# ProPrj_LowFreqInverter_2025-11-08.net
KiCad netlist of a schematic drawn in EasyEDA Pro
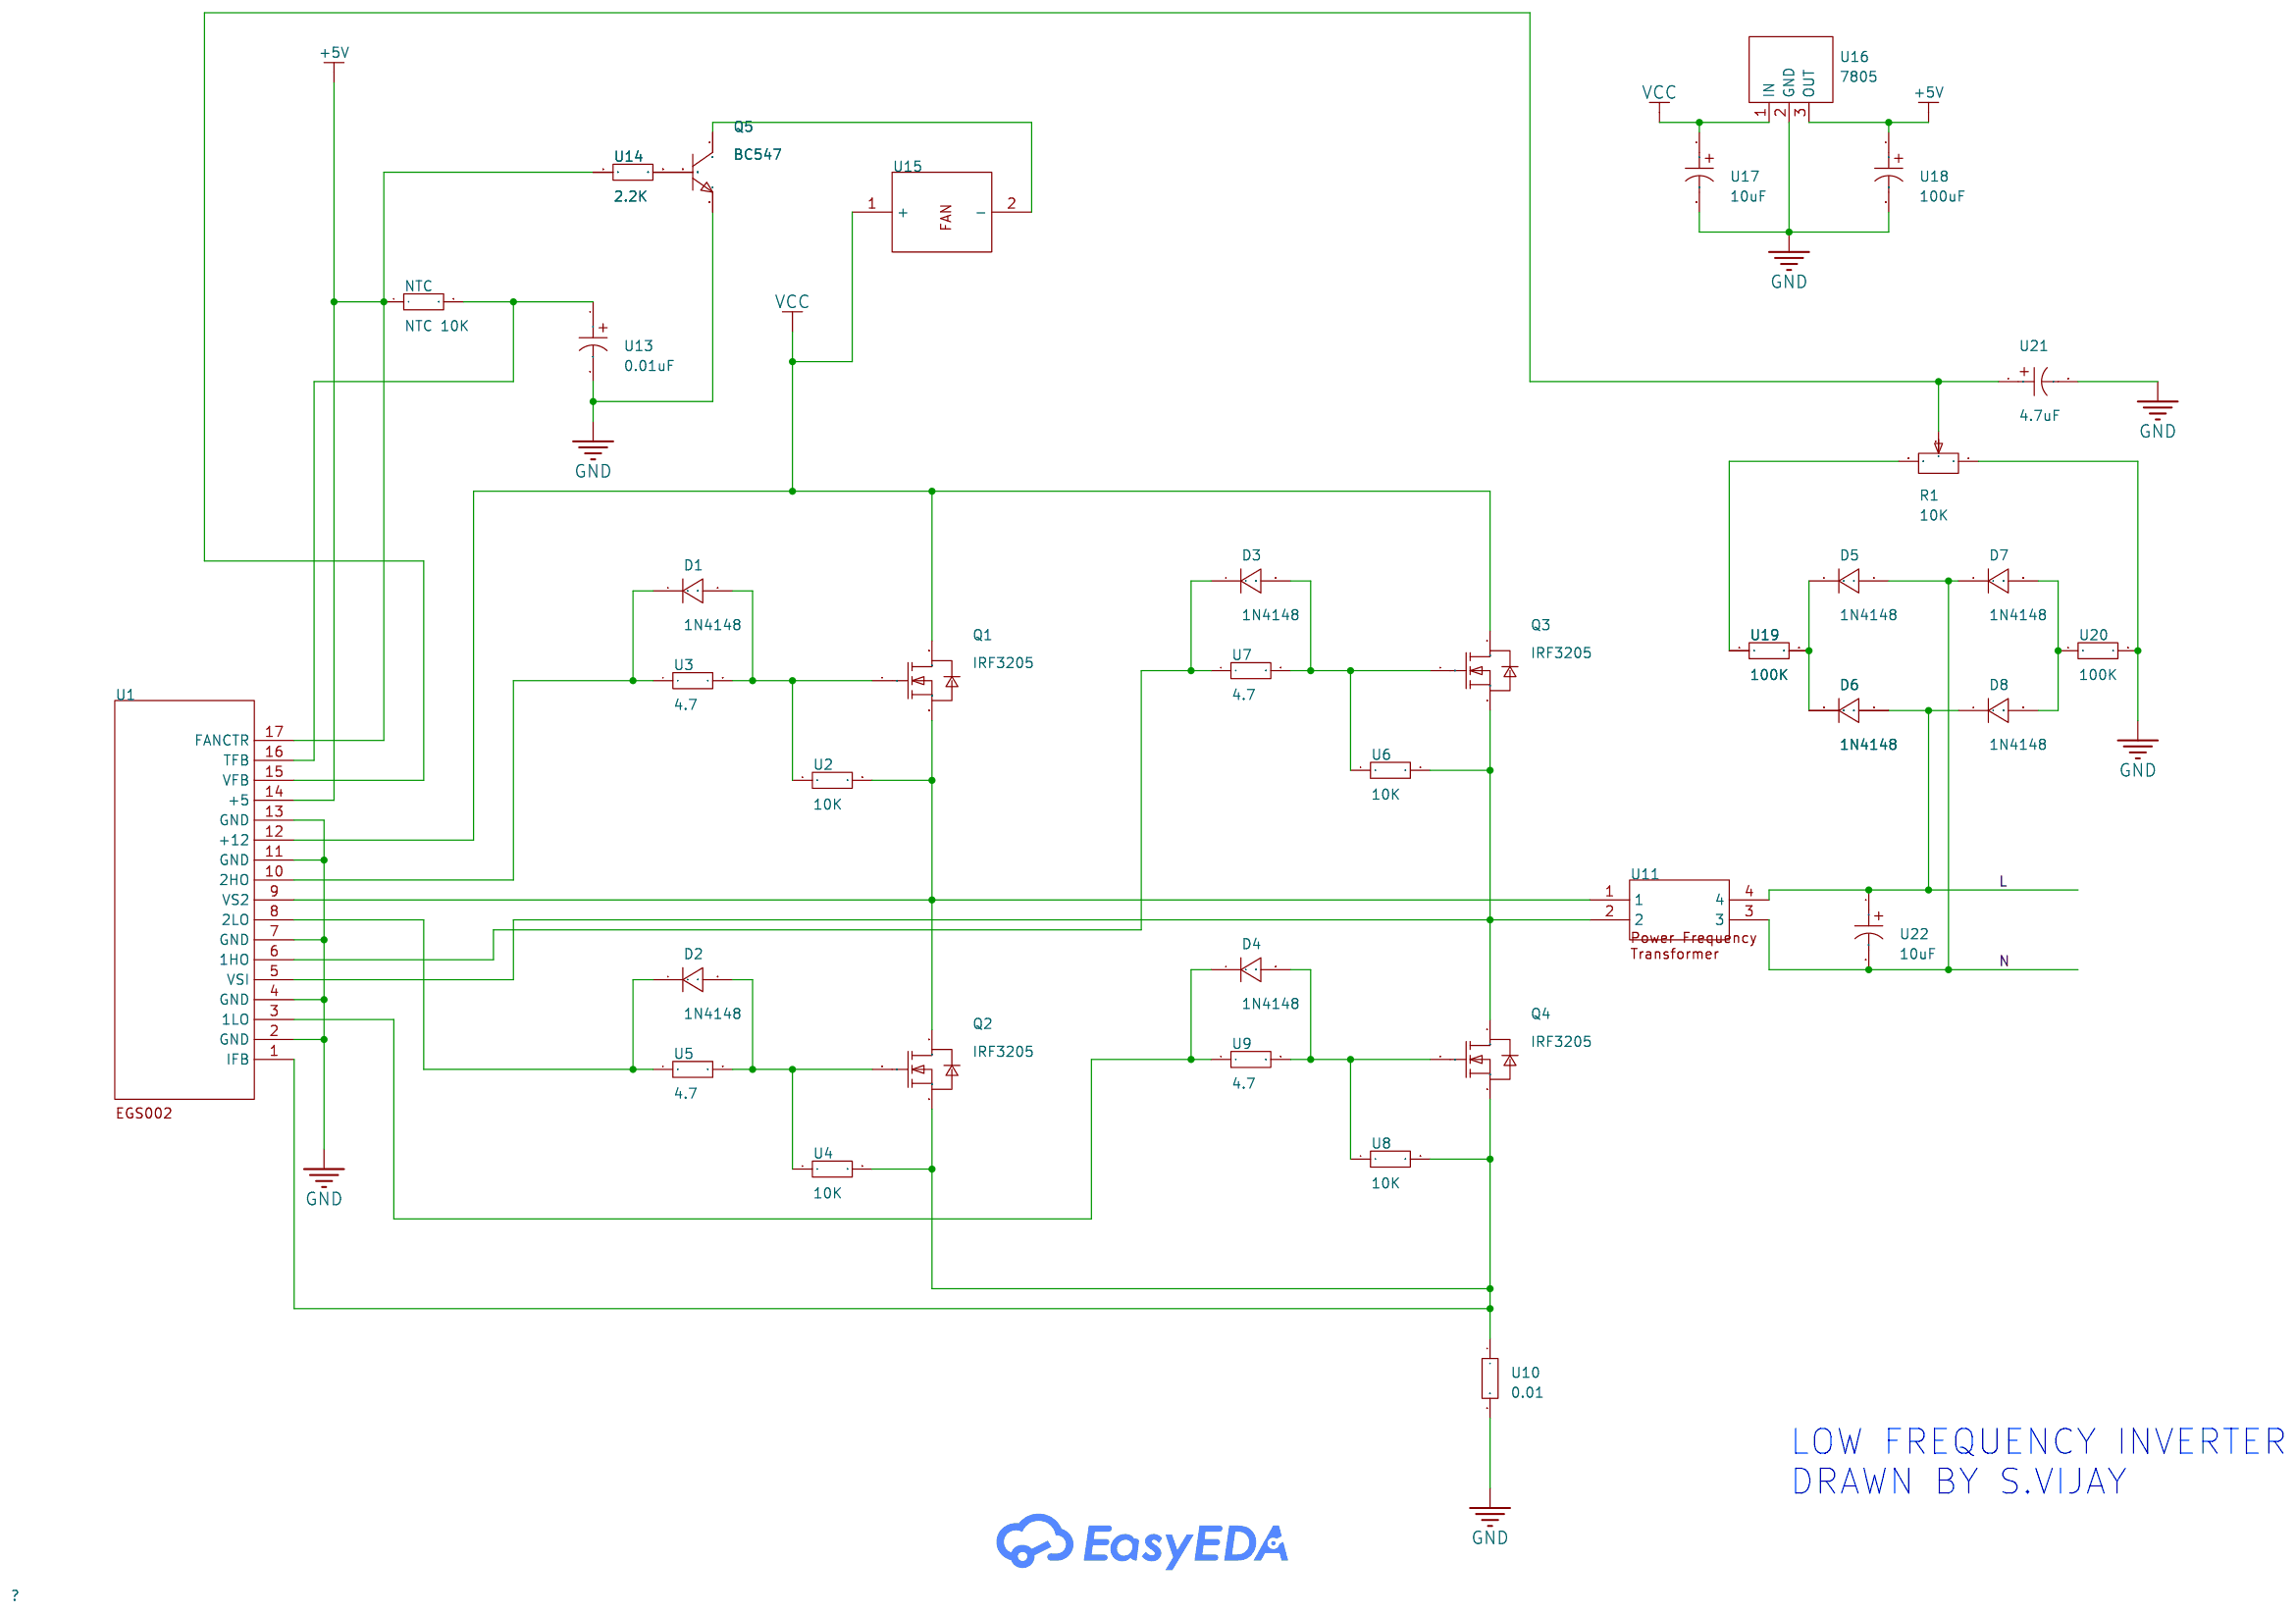
[diagram p0: schematic sheet]

(export (version "E")
  (design (tool "Eeschema 10.0.6"))
  (components
    (comp (ref "D1")
      (value "1N4148")
      (footprint "easyedapro:DO-35_BD2.0-L4.0-P8.0-D0.5-RD")
      (libsource (lib "easyedapro") (part "1N4148_C13769"))
    )
    (comp (ref "D2")
      (value "1N4148")
      (footprint "easyedapro:DO-35_BD2.0-L4.0-P8.0-D0.5-RD")
      (libsource (lib "easyedapro") (part "1N4148_C13769"))
    )
    (comp (ref "D3")
      (value "1N4148")
      (footprint "easyedapro:DO-35_BD2.0-L4.0-P8.0-D0.5-RD")
      (libsource (lib "easyedapro") (part "1N4148_C13769"))
    )
    (comp (ref "D4")
      (value "1N4148")
      (footprint "easyedapro:DO-35_BD2.0-L4.0-P8.0-D0.5-RD")
      (libsource (lib "easyedapro") (part "1N4148_C13769"))
    )
    (comp (ref "D5")
      (value "1N4148")
      (footprint "easyedapro:DO-35_BD2.0-L4.0-P8.0-D0.5-RD")
      (libsource (lib "easyedapro") (part "1N4148_C13769"))
    )
    (comp (ref "D6")
      (value "1N4148")
      (footprint "easyedapro:DO-35_BD2.0-L4.0-P8.0-D0.5-RD")
      (libsource (lib "easyedapro") (part "1N4148_C13769"))
    )
    (comp (ref "D7")
      (value "1N4148")
      (footprint "easyedapro:DO-35_BD2.0-L4.0-P8.0-D0.5-RD")
      (libsource (lib "easyedapro") (part "1N4148_C13769"))
    )
    (comp (ref "D8")
      (value "1N4148")
      (footprint "easyedapro:DO-35_BD2.0-L4.0-P8.0-D0.5-RD")
      (libsource (lib "easyedapro") (part "1N4148_C13769"))
    )
    (comp (ref "NTC")
      (value "NTC 10K")
      (footprint "easyedapro:RES-TH_BD2.3-L6.5-P10.50-D0.5")
      (fields (field (name "Manufacturer Part") "RES1/4W47K"))
      (libsource (lib "easyedapro") (part "RES1/4W47K"))
    )
    (comp (ref "Q1")
      (value "IRF3205")
      (footprint "easyedapro:TO-220-3_L10.0-W4.6-P2.54-L")
      (fields (field (name "Manufacturer") "minos(迈诺斯)"))
      (libsource (lib "easyedapro") (part "IRF3205"))
    )
    (comp (ref "Q2")
      (value "IRF3205")
      (footprint "easyedapro:TO-220-3_L10.0-W4.6-P2.54-L")
      (fields (field (name "Manufacturer") "minos(迈诺斯)"))
      (libsource (lib "easyedapro") (part "IRF3205"))
    )
    (comp (ref "Q3")
      (value "IRF3205")
      (footprint "easyedapro:TO-220-3_L10.0-W4.6-P2.54-L")
      (fields (field (name "Manufacturer") "minos(迈诺斯)"))
      (libsource (lib "easyedapro") (part "IRF3205"))
    )
    (comp (ref "Q4")
      (value "IRF3205")
      (footprint "easyedapro:TO-220-3_L10.0-W4.6-P2.54-L")
      (fields (field (name "Manufacturer") "minos(迈诺斯)"))
      (libsource (lib "easyedapro") (part "IRF3205"))
    )
    (comp (ref "Q5")
      (value "BC547")
      (footprint "easyedapro:TO-92-3_L4.9-W3.7-P1.27-L")
      (fields (field (name "Manufacturer") "CJ(江苏长电/长晶)"))
      (libsource (lib "easyedapro") (part "BC547_C47089404"))
    )
    (comp (ref "R1")
      (value "10K")
      (footprint "easyedapro:RES-ADJ-TH_3296W")
      (libsource (lib "easyedapro") (part "3296W-2K"))
    )
    (comp (ref "U1")
      (value "~")
      (footprint "easyedapro:EGS002")
      (libsource (lib "easyedapro") (part "EGS002"))
    )
    (comp (ref "U2")
      (value "10K")
      (footprint "easyedapro:RES-TH_BD2.3-L6.5-P10.50-D0.5")
      (fields (field (name "Manufacturer Part") "RES1/4W47K"))
      (libsource (lib "easyedapro") (part "RES1/4W47K"))
    )
    (comp (ref "U3")
      (value "4.7")
      (footprint "easyedapro:RES-TH_BD2.3-L6.5-P10.50-D0.5")
      (libsource (lib "easyedapro") (part "RES1/4W47K"))
    )
    (comp (ref "U4")
      (value "10K")
      (footprint "easyedapro:RES-TH_BD2.3-L6.5-P10.50-D0.5")
      (fields (field (name "Manufacturer Part") "RES1/4W47K"))
      (libsource (lib "easyedapro") (part "RES1/4W47K"))
    )
    (comp (ref "U5")
      (value "4.7")
      (footprint "easyedapro:RES-TH_BD2.3-L6.5-P10.50-D0.5")
      (libsource (lib "easyedapro") (part "RES1/4W47K"))
    )
    (comp (ref "U6")
      (value "10K")
      (footprint "easyedapro:RES-TH_BD2.3-L6.5-P10.50-D0.5")
      (fields (field (name "Manufacturer Part") "RES1/4W47K"))
      (libsource (lib "easyedapro") (part "RES1/4W47K"))
    )
    (comp (ref "U7")
      (value "4.7")
      (footprint "easyedapro:RES-TH_BD2.3-L6.5-P10.50-D0.5")
      (libsource (lib "easyedapro") (part "RES1/4W47K"))
    )
    (comp (ref "U8")
      (value "10K")
      (footprint "easyedapro:RES-TH_BD2.3-L6.5-P10.50-D0.5")
      (fields (field (name "Manufacturer Part") "RES1/4W47K"))
      (libsource (lib "easyedapro") (part "RES1/4W47K"))
    )
    (comp (ref "U9")
      (value "4.7")
      (footprint "easyedapro:RES-TH_BD2.3-L6.5-P10.50-D0.5")
      (libsource (lib "easyedapro") (part "RES1/4W47K"))
    )
    (comp (ref "U10")
      (value "0.01")
      (footprint "easyedapro:RES-TH_BD2.3-L6.5-P10.50-D0.5")
      (libsource (lib "easyedapro") (part "RES1/4W47K"))
    )
    (comp (ref "U11")
      (value "~")
      (footprint "easyedapro:Power Frequency Transformer")
      (libsource (lib "easyedapro") (part "Power Frequency Transformer"))
    )
    (comp (ref "U13")
      (value "0.01uF")
      (footprint "easyedapro:CAP-TH_BD5.0-P2.00-D0.6-FD")
      (libsource (lib "easyedapro") (part "CE2.5MM-4.7UF 50V"))
    )
    (comp (ref "U14")
      (value "2.2K")
      (footprint "easyedapro:RES-TH_BD2.3-L6.5-P10.50-D0.5")
      (fields (field (name "Manufacturer Part") "RES1/4W47K"))
      (libsource (lib "easyedapro") (part "RES1/4W47K"))
    )
    (comp (ref "U15") (value "~") (footprint "easyedapro:FAN") (libsource (lib "easyedapro") (part "FAN")))
    (comp (ref "U16")
      (value "7805")
      (footprint "easyedapro:TO-220-3_L10.2-W4.5-P2.54-L")
      (libsource (lib "easyedapro") (part "7805_C2941265"))
    )
    (comp (ref "U17")
      (value "10uF")
      (footprint "easyedapro:CAP-TH_BD5.0-P2.00-D0.6-FD")
      (libsource (lib "easyedapro") (part "CE2.5MM-4.7UF 50V"))
    )
    (comp (ref "U18")
      (value "100uF")
      (footprint "easyedapro:CAP-TH_BD5.0-P2.00-D0.6-FD")
      (libsource (lib "easyedapro") (part "CE2.5MM-4.7UF 50V"))
    )
    (comp (ref "U19")
      (value "100K")
      (footprint "easyedapro:RES-TH_BD2.3-L6.5-P10.50-D0.5")
      (fields (field (name "Manufacturer Part") "RES1/4W47K"))
      (libsource (lib "easyedapro") (part "RES1/4W47K"))
    )
    (comp (ref "U20")
      (value "100K")
      (footprint "easyedapro:RES-TH_BD2.3-L6.5-P10.50-D0.5")
      (fields (field (name "Manufacturer Part") "RES1/4W47K"))
      (libsource (lib "easyedapro") (part "RES1/4W47K"))
    )
    (comp (ref "U21")
      (value "4.7uF")
      (footprint "easyedapro:CAP-TH_BD5.0-P2.00-D0.6-FD")
      (libsource (lib "easyedapro") (part "CE2.5MM-4.7UF 50V"))
    )
    (comp (ref "U22")
      (value "10uF")
      (footprint "easyedapro:CAP-TH_BD5.0-P2.00-D0.6-FD")
      (libsource (lib "easyedapro") (part "CE2.5MM-4.7UF 50V"))
    )
  )
  (nets
    (net (code "1") (name "+5V") (class "Default")
      (node (ref "NTC") (pin "1") (pinfunction "1_1") (pintype "input"))
      (node (ref "U1") (pin "14") (pinfunction "+5_14") (pintype "input"))
      (node (ref "U1") (pin "17") (pinfunction "FANCTR_17") (pintype "input"))
      (node (ref "U14") (pin "1") (pinfunction "1_1") (pintype "input"))
      (node (ref "U16") (pin "3") (pinfunction "OUT_3") (pintype "unspecified"))
      (node (ref "U18") (pin "1") (pinfunction "1_1") (pintype "input"))
    )
    (net (code "2") (name "/L") (class "Default")
      (node (ref "D6") (pin "2") (pinfunction "2_2") (pintype "unspecified"))
      (node (ref "D8") (pin "1") (pinfunction "1_1") (pintype "unspecified"))
      (node (ref "U11") (pin "4") (pinfunction "4_4") (pintype "input"))
      (node (ref "U22") (pin "1") (pinfunction "1_1") (pintype "input"))
    )
    (net (code "3") (name "/N") (class "Default")
      (node (ref "D5") (pin "2") (pinfunction "2_2") (pintype "unspecified"))
      (node (ref "D7") (pin "1") (pinfunction "1_1") (pintype "unspecified"))
      (node (ref "U11") (pin "3") (pinfunction "3_3") (pintype "input"))
      (node (ref "U22") (pin "2") (pinfunction "2_2") (pintype "input"))
    )
    (net (code "4") (name "GND") (class "Default")
      (node (ref "Q5") (pin "3") (pinfunction "E_3") (pintype "input"))
      (node (ref "R1") (pin "1") (pinfunction "1_1") (pintype "input"))
      (node (ref "U1") (pin "11") (pinfunction "GND_11") (pintype "input"))
      (node (ref "U1") (pin "13") (pinfunction "GND_13") (pintype "input"))
      (node (ref "U1") (pin "2") (pinfunction "GND_2") (pintype "input"))
      (node (ref "U1") (pin "4") (pinfunction "GND_4") (pintype "input"))
      (node (ref "U1") (pin "7") (pinfunction "GND_7") (pintype "input"))
      (node (ref "U10") (pin "2") (pinfunction "2_2") (pintype "input"))
      (node (ref "U13") (pin "2") (pinfunction "2_2") (pintype "input"))
      (node (ref "U16") (pin "2") (pinfunction "GND_2") (pintype "unspecified"))
      (node (ref "U17") (pin "2") (pinfunction "2_2") (pintype "input"))
      (node (ref "U18") (pin "2") (pinfunction "2_2") (pintype "input"))
      (node (ref "U20") (pin "2") (pinfunction "2_2") (pintype "input"))
      (node (ref "U21") (pin "2") (pinfunction "2_2") (pintype "input"))
    )
    (net (code "5") (name "Net-(D5-Pad1)") (class "Default")
      (node (ref "D5") (pin "1") (pinfunction "1_1") (pintype "unspecified"))
      (node (ref "D6") (pin "1") (pinfunction "1_1") (pintype "unspecified"))
      (node (ref "U19") (pin "2") (pinfunction "2_2") (pintype "input"))
    )
    (net (code "6") (name "Net-(D7-Pad2)") (class "Default")
      (node (ref "D7") (pin "2") (pinfunction "2_2") (pintype "unspecified"))
      (node (ref "D8") (pin "2") (pinfunction "2_2") (pintype "unspecified"))
      (node (ref "U20") (pin "1") (pinfunction "1_1") (pintype "input"))
    )
    (net (code "7") (name "Net-(Q1-G)") (class "Default")
      (node (ref "D1") (pin "2") (pinfunction "2_2") (pintype "unspecified"))
      (node (ref "Q1") (pin "1") (pinfunction "G_1") (pintype "unspecified"))
      (node (ref "U2") (pin "1") (pinfunction "1_1") (pintype "input"))
      (node (ref "U3") (pin "2") (pinfunction "2_2") (pintype "input"))
    )
    (net (code "8") (name "Net-(Q1-S)") (class "Default")
      (node (ref "Q1") (pin "3") (pinfunction "S_3") (pintype "unspecified"))
      (node (ref "Q2") (pin "2") (pinfunction "D_2") (pintype "unspecified"))
      (node (ref "U1") (pin "9") (pinfunction "VS2_9") (pintype "input"))
      (node (ref "U11") (pin "1") (pinfunction "1_1") (pintype "input"))
      (node (ref "U2") (pin "2") (pinfunction "2_2") (pintype "input"))
    )
    (net (code "9") (name "Net-(Q2-G)") (class "Default")
      (node (ref "D2") (pin "2") (pinfunction "2_2") (pintype "unspecified"))
      (node (ref "Q2") (pin "1") (pinfunction "G_1") (pintype "unspecified"))
      (node (ref "U4") (pin "1") (pinfunction "1_1") (pintype "input"))
      (node (ref "U5") (pin "2") (pinfunction "2_2") (pintype "input"))
    )
    (net (code "10") (name "Net-(Q2-S)") (class "Default")
      (node (ref "Q2") (pin "3") (pinfunction "S_3") (pintype "unspecified"))
      (node (ref "Q4") (pin "3") (pinfunction "S_3") (pintype "unspecified"))
      (node (ref "U1") (pin "1") (pinfunction "IFB_1") (pintype "input"))
      (node (ref "U10") (pin "1") (pinfunction "1_1") (pintype "input"))
      (node (ref "U4") (pin "2") (pinfunction "2_2") (pintype "input"))
      (node (ref "U8") (pin "2") (pinfunction "2_2") (pintype "input"))
    )
    (net (code "11") (name "Net-(Q3-G)") (class "Default")
      (node (ref "D3") (pin "2") (pinfunction "2_2") (pintype "unspecified"))
      (node (ref "Q3") (pin "1") (pinfunction "G_1") (pintype "unspecified"))
      (node (ref "U6") (pin "1") (pinfunction "1_1") (pintype "input"))
      (node (ref "U7") (pin "2") (pinfunction "2_2") (pintype "input"))
    )
    (net (code "12") (name "Net-(Q3-S)") (class "Default")
      (node (ref "Q3") (pin "3") (pinfunction "S_3") (pintype "unspecified"))
      (node (ref "Q4") (pin "2") (pinfunction "D_2") (pintype "unspecified"))
      (node (ref "U1") (pin "5") (pinfunction "VSI_5") (pintype "input"))
      (node (ref "U11") (pin "2") (pinfunction "2_2") (pintype "input"))
      (node (ref "U6") (pin "2") (pinfunction "2_2") (pintype "input"))
    )
    (net (code "13") (name "Net-(Q4-G)") (class "Default")
      (node (ref "D4") (pin "2") (pinfunction "2_2") (pintype "unspecified"))
      (node (ref "Q4") (pin "1") (pinfunction "G_1") (pintype "unspecified"))
      (node (ref "U8") (pin "1") (pinfunction "1_1") (pintype "input"))
      (node (ref "U9") (pin "2") (pinfunction "2_2") (pintype "input"))
    )
    (net (code "14") (name "Net-(Q5-B)") (class "Default")
      (node (ref "Q5") (pin "2") (pinfunction "B_2") (pintype "input"))
      (node (ref "U14") (pin "2") (pinfunction "2_2") (pintype "input"))
    )
    (net (code "15") (name "Net-(Q5-C)") (class "Default")
      (node (ref "Q5") (pin "1") (pinfunction "C_1") (pintype "input"))
      (node (ref "U15") (pin "2") (pinfunction "-_2") (pintype "input"))
    )
    (net (code "16") (name "Net-(R1-Pad3)") (class "Default")
      (node (ref "R1") (pin "3") (pinfunction "3_3") (pintype "input"))
      (node (ref "U19") (pin "1") (pinfunction "1_1") (pintype "input"))
    )
    (net (code "17") (name "Net-(U1-1HO)") (class "Default")
      (node (ref "D3") (pin "1") (pinfunction "1_1") (pintype "unspecified"))
      (node (ref "U1") (pin "6") (pinfunction "1HO_6") (pintype "input"))
      (node (ref "U7") (pin "1") (pinfunction "1_1") (pintype "input"))
    )
    (net (code "18") (name "Net-(U1-1LO)") (class "Default")
      (node (ref "D4") (pin "1") (pinfunction "1_1") (pintype "unspecified"))
      (node (ref "U1") (pin "3") (pinfunction "1LO_3") (pintype "input"))
      (node (ref "U9") (pin "1") (pinfunction "1_1") (pintype "input"))
    )
    (net (code "19") (name "Net-(U1-2HO)") (class "Default")
      (node (ref "D1") (pin "1") (pinfunction "1_1") (pintype "unspecified"))
      (node (ref "U1") (pin "10") (pinfunction "2HO_10") (pintype "input"))
      (node (ref "U3") (pin "1") (pinfunction "1_1") (pintype "input"))
    )
    (net (code "20") (name "Net-(U1-2LO)") (class "Default")
      (node (ref "D2") (pin "1") (pinfunction "1_1") (pintype "unspecified"))
      (node (ref "U1") (pin "8") (pinfunction "2LO_8") (pintype "input"))
      (node (ref "U5") (pin "1") (pinfunction "1_1") (pintype "input"))
    )
    (net (code "21") (name "Net-(U1-TFB)") (class "Default")
      (node (ref "NTC") (pin "2") (pinfunction "2_2") (pintype "input"))
      (node (ref "U1") (pin "16") (pinfunction "TFB_16") (pintype "input"))
      (node (ref "U13") (pin "1") (pinfunction "1_1") (pintype "input"))
    )
    (net (code "22") (name "Net-(U1-VFB)") (class "Default")
      (node (ref "R1") (pin "2") (pinfunction "2_2") (pintype "input"))
      (node (ref "U1") (pin "15") (pinfunction "VFB_15") (pintype "input"))
      (node (ref "U21") (pin "1") (pinfunction "1_1") (pintype "input"))
    )
    (net (code "23") (name "VCC") (class "Default")
      (node (ref "Q1") (pin "2") (pinfunction "D_2") (pintype "unspecified"))
      (node (ref "Q3") (pin "2") (pinfunction "D_2") (pintype "unspecified"))
      (node (ref "U1") (pin "12") (pinfunction "+12_12") (pintype "input"))
      (node (ref "U15") (pin "1") (pinfunction "+_1") (pintype "input"))
      (node (ref "U16") (pin "1") (pinfunction "IN_1") (pintype "unspecified"))
      (node (ref "U17") (pin "1") (pinfunction "1_1") (pintype "input"))
    )
  )
)
